# schmatic.net
KiCad netlist of a schematic drawn in Altium Designer
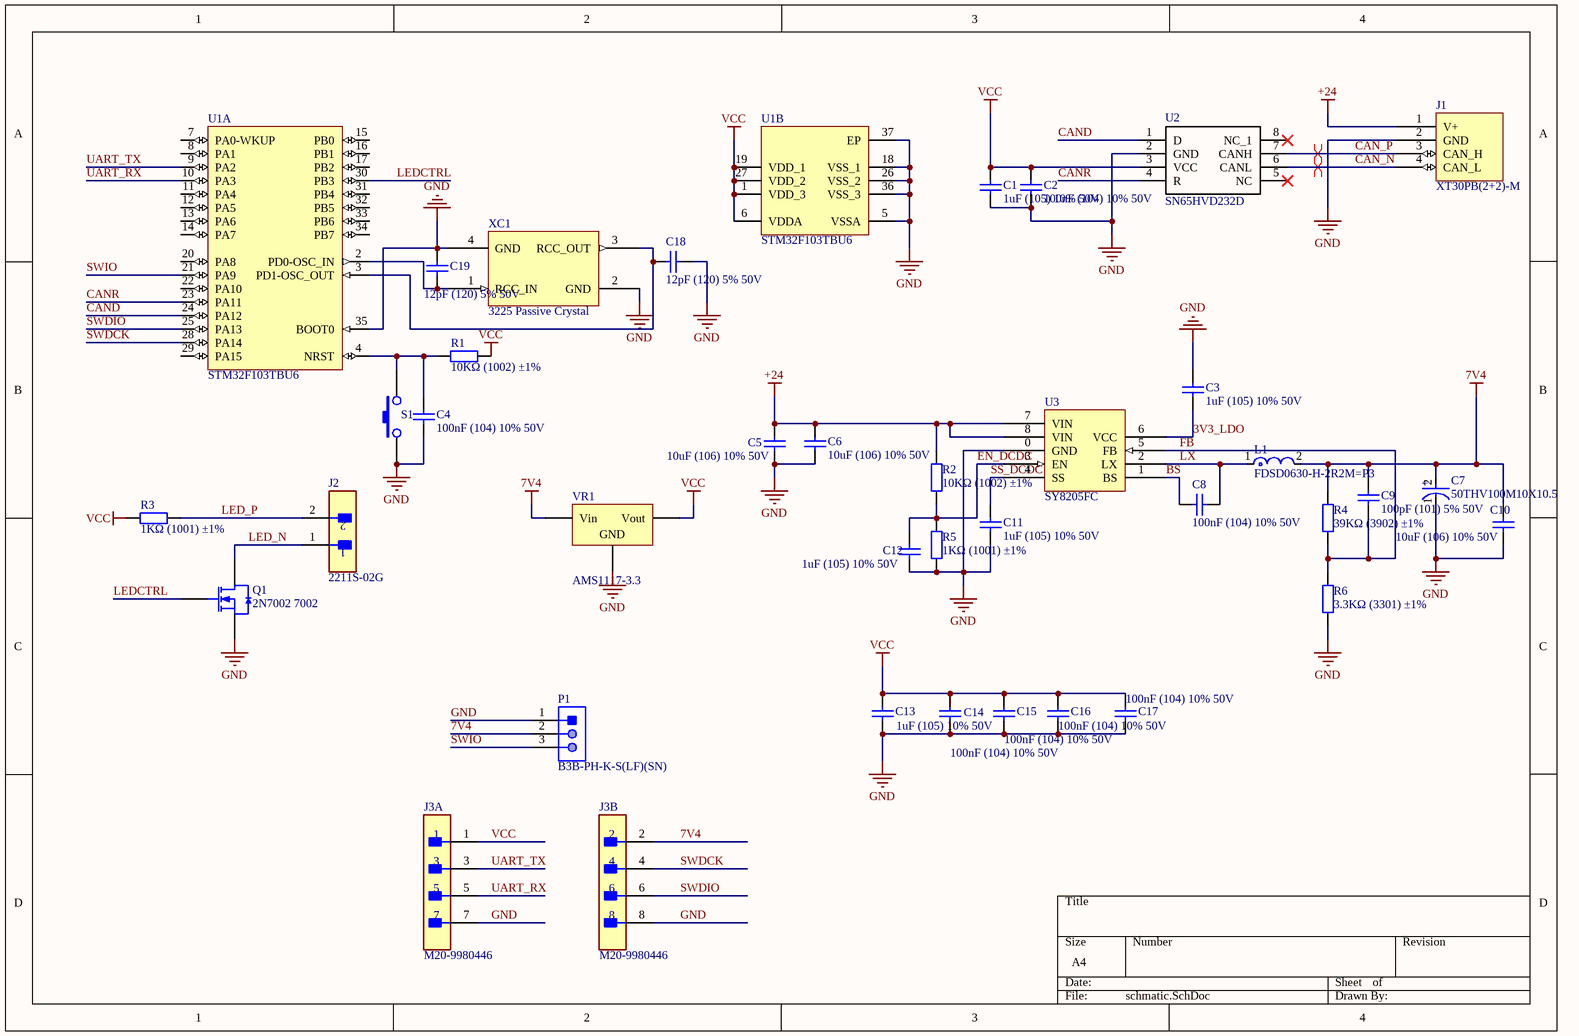
[diagram p0: schmatic.SchDoc]

(export (version "E")
  (design (tool "Eeschema 10.0.6"))
  (components
    (comp (ref "C1")
      (value "1uF (105) 10% 50V")
      (footprint "0603_C")
      (description "贴片电容")
      (libsource (lib "Miscellaneous Devices LC") (part "0603 1uF (105) 10% 50V"))
    )
    (comp (ref "C2")
      (value "100nF (104) 10% 50V")
      (footprint "0603_C")
      (description "贴片电容")
      (libsource (lib "Miscellaneous Devices LC") (part "0603 100nF (104) 10% 50V"))
    )
    (comp (ref "C3")
      (value "1uF (105) 10% 50V")
      (footprint "0603_C")
      (description "贴片电容")
      (libsource (lib "Miscellaneous Devices LC") (part "0603 1uF (105) 10% 50V"))
    )
    (comp (ref "C4")
      (value "100nF (104) 10% 50V")
      (footprint "0603_C")
      (description "贴片电容")
      (libsource (lib "Miscellaneous Devices LC") (part "0603 100nF (104) 10% 50V"))
    )
    (comp (ref "C5")
      (value "10uF (106) 10% 50V")
      (footprint "1206_C")
      (description "贴片电容")
      (libsource (lib "Miscellaneous Devices LC") (part "1206 10uF (106) 10% 50V"))
    )
    (comp (ref "C6")
      (value "10uF (106) 10% 50V")
      (footprint "1206_C")
      (description "贴片电容")
      (libsource (lib "Miscellaneous Devices LC") (part "1206 10uF (106) 10% 50V"))
    )
    (comp (ref "C7")
      (value "50THV100M10X10.5")
      (footprint "FP-THV10X10_5-MFG")
      (description "CAP ALUM 100UF 20% 50V SMD")
      (fields (field (name "VOLTAGE") "50V") (field (name "TOLERANCE") "20%"))
      (libsource (lib "Altium Content Vault") (part "203bc49f2ac43e59fd269a8c329ed05"))
    )
    (comp (ref "C8")
      (value "100nF (104) 10% 50V")
      (footprint "0603_C")
      (description "贴片电容")
      (libsource (lib "Miscellaneous Devices LC") (part "0603 100nF (104) 10% 50V"))
    )
    (comp (ref "C9")
      (value "100pF (101) 5% 50V")
      (footprint "0603_C")
      (description "贴片电容")
      (libsource (lib "Miscellaneous Devices LC") (part "0603 100pF (101) 5% 50V"))
    )
    (comp (ref "C10")
      (value "10uF (106) 10% 50V")
      (footprint "1206_C")
      (description "贴片电容")
      (libsource (lib "Miscellaneous Devices LC") (part "1206 10uF (106) 10% 50V"))
    )
    (comp (ref "C11")
      (value "1uF (105) 10% 50V")
      (footprint "0603_C")
      (description "贴片电容")
      (libsource (lib "Miscellaneous Devices LC") (part "0603 1uF (105) 10% 50V"))
    )
    (comp (ref "C12")
      (value "1uF (105) 10% 50V")
      (footprint "0603_C")
      (description "贴片电容")
      (libsource (lib "Miscellaneous Devices LC") (part "0603 1uF (105) 10% 50V"))
    )
    (comp (ref "C13")
      (value "1uF (105) 10% 50V")
      (footprint "0603_C")
      (description "贴片电容")
      (libsource (lib "Miscellaneous Devices LC") (part "0603 1uF (105) 10% 50V"))
    )
    (comp (ref "C14")
      (value "100nF (104) 10% 50V")
      (footprint "0603_C")
      (description "贴片电容")
      (libsource (lib "Miscellaneous Devices LC") (part "0603 100nF (104) 10% 50V"))
    )
    (comp (ref "C15")
      (value "100nF (104) 10% 50V")
      (footprint "0603_C")
      (description "贴片电容")
      (libsource (lib "Miscellaneous Devices LC") (part "0603 100nF (104) 10% 50V"))
    )
    (comp (ref "C16")
      (value "100nF (104) 10% 50V")
      (footprint "0603_C")
      (description "贴片电容")
      (libsource (lib "Miscellaneous Devices LC") (part "0603 100nF (104) 10% 50V"))
    )
    (comp (ref "C17")
      (value "100nF (104) 10% 50V")
      (footprint "0603_C")
      (description "贴片电容")
      (libsource (lib "Miscellaneous Devices LC") (part "0603 100nF (104) 10% 50V"))
    )
    (comp (ref "C18")
      (value "12pF (120) 5% 50V")
      (footprint "0603_C")
      (description "贴片电容")
      (libsource (lib "Miscellaneous Devices LC") (part "0603 12pF (120) 5% 50V"))
    )
    (comp (ref "C19")
      (value "12pF (120) 5% 50V")
      (footprint "0603_C")
      (description "贴片电容")
      (libsource (lib "Miscellaneous Devices LC") (part "0603 12pF (120) 5% 50V"))
    )
    (comp (ref "J1")
      (value "XT30PB(2+2)-M")
      (footprint "XT30PB(2+2)-M-Footprint-1")
      (description "This is a power connector that can also be used to send/receive can signals")
      (libsource (lib "Skyli Personal Workspace") (part "XT30PB(2+2)-M"))
    )
    (comp (ref "J2")
      (value "2211S-02G")
      (footprint "FP-2211S-02G-MFG")
      (description "2.54mm pitch, single row PCB headers.")
      (libsource (lib "Altium Content Vault") (part "3bc925449376181038e59eaffc5286c"))
    )
    (comp (ref "J3")
      (value "M20-9980446")
      (footprint "FP-M20-9980446-MFG")
      (description "CONN HEADER VERT 8POS 2.54MM")
      (libsource (lib "Altium Content Vault") (part "811e954b9c034aa737de4d9295cbe7e"))
    )
    (comp (ref "L1")
      (value "FDSD0630-H-2R2M=P3")
      (footprint "FP-FDSD0630-MFG")
      (description "FIXED IND 2.2UH 7.1A 17 MOHM SMD")
      (fields (field (name "TOLERANCE") "20%"))
      (libsource (lib "Altium Content Vault") (part "4cc4b267dca4c8e51f7102f422741d8"))
    )
    (comp (ref "P1")
      (value "B3B-PH-K-S(LF)(SN)")
      (footprint "JST-B3B-PH-K-S-3_V")
      (fields (field (name "MANUFACTURER") "JST"))
      (libsource (lib "Altium Content Vault") (part "CN-1P-M-R3"))
    )
    (comp (ref "Q1")
      (value "2N7002 7002")
      (footprint "SOT-23(SOT-23-3)")
      (description "MOS(场效应管)")
      (libsource (lib "Miscellaneous Devices LC") (part "2N7002 7002"))
    )
    (comp (ref "R1")
      (value "10KΩ (1002) ±1%")
      (footprint "0603_R")
      (description "贴片电阻")
      (libsource (lib "") (part "0603 10KΩ (1002) 1%_1"))
    )
    (comp (ref "R2")
      (value "10KΩ (1002) ±1%")
      (footprint "0603_R")
      (description "贴片电阻")
      (libsource (lib "Miscellaneous Devices LC") (part "0603 10KΩ (1002) 1%"))
    )
    (comp (ref "R3")
      (value "1KΩ (1001) ±1%")
      (footprint "0603_R")
      (description "贴片电阻")
      (libsource (lib "") (part "0603 1KΩ (1001) 1%_1"))
    )
    (comp (ref "R4")
      (value "39KΩ (3902) ±1%")
      (footprint "0603_R")
      (description "贴片电阻")
      (libsource (lib "Miscellaneous Devices LC") (part "0603 39KΩ (3902) 1%"))
    )
    (comp (ref "R5")
      (value "1KΩ (1001) ±1%")
      (footprint "0603_R")
      (description "贴片电阻")
      (libsource (lib "Miscellaneous Devices LC") (part "0603 1KΩ (1001) 1%"))
    )
    (comp (ref "R6")
      (value "3.3KΩ (3301) ±1%")
      (footprint "0603_R")
      (description "贴片电阻")
      (libsource (lib "Miscellaneous Devices LC") (part "0603 3.3KΩ (3301) 1%"))
    )
    (comp (ref "S1") (value "按键") (footprint "SWT3*4") (libsource (lib "libadp") (part "Button")))
    (comp (ref "U1")
      (value "STM32F103TBU6")
      (footprint "STM-VFQFPN36_L")
      (libsource (lib "Altium Content Vault") (part "MC-ARM-STM32F103X8_B-SQ37"))
    )
    (comp (ref "U2")
      (value "SN65HVD232D")
      (footprint "SOIC127P600X175-8N")
      (description "3.3-V CAN TRANSCEIVER")
      (fields (field (name "MOUSER PART NUMBER") "595-SN65HVD232D") (field (name "RS PART NUMBER") "1977506"))
      (libsource (lib "libadp") (part "SN65HVD232D"))
    )
    (comp (ref "U3")
      (value "SY8205FC")
      (footprint "SOP-8_EP_150mil")
      (description "5A, 4.5V-30V Input, Synchronous Step Down Regulator (Buck)")
      (libsource (lib "libadp") (part "SY8205FC"))
    )
    (comp (ref "VR1")
      (value "AMS1117-3.3")
      (footprint "SOT-223")
      (description "低压差线性稳压(LDO)")
      (libsource (lib "Miscellaneous Devices LC") (part "SOT-223 AMS1117-3.3"))
    )
    (comp (ref "XC1")
      (value "3225 Passive Crystal")
      (footprint "SMD-3225")
      (libsource (lib "libadp") (part "3225 Passive Crystal"))
    )
  )
  (nets
    (net (code "1") (name "+24") (class "Default")
      (node (ref "C5") (pin "2") (pinfunction "2_2") (pintype "passive"))
      (node (ref "C6") (pin "2") (pinfunction "2_2") (pintype "passive"))
      (node (ref "J1") (pin "1") (pinfunction "V+_1") (pintype "power_in"))
      (node (ref "R2") (pin "2") (pinfunction "2_2") (pintype "passive"))
      (node (ref "U3") (pin "7") (pinfunction "VIN_7") (pintype "power_in"))
      (node (ref "U3") (pin "8") (pinfunction "VIN_8") (pintype "power_in"))
    )
    (net (code "2") (name "/3V3_LDO") (class "Default")
      (node (ref "C3") (pin "1") (pinfunction "1_1") (pintype "passive"))
      (node (ref "U3") (pin "6") (pinfunction "VCC_6") (pintype "power_in"))
    )
    (net (code "3") (name "/BS") (class "Default")
      (node (ref "C8") (pin "1") (pinfunction "1_1") (pintype "passive"))
      (node (ref "U3") (pin "1") (pinfunction "BS_1") (pintype "power_in"))
    )
    (net (code "4") (name "/CAND") (class "Default")
      (node (ref "U1") (pin "24") (pinfunction "PA12_24") (pintype "bidirectional"))
      (node (ref "U2") (pin "1") (pinfunction "D_1") (pintype "passive"))
    )
    (net (code "5") (name "/CANR") (class "Default")
      (node (ref "U1") (pin "23") (pinfunction "PA11_23") (pintype "bidirectional"))
      (node (ref "U2") (pin "4") (pinfunction "R_4") (pintype "passive"))
    )
    (net (code "6") (name "/CAN_N") (class "Default")
      (node (ref "J1") (pin "4") (pinfunction "CAN_L_4") (pintype "bidirectional"))
      (node (ref "U2") (pin "6") (pinfunction "CANL_6") (pintype "passive"))
    )
    (net (code "7") (name "/CAN_P") (class "Default")
      (node (ref "J1") (pin "3") (pinfunction "CAN_H_3") (pintype "bidirectional"))
      (node (ref "U2") (pin "7") (pinfunction "CANH_7") (pintype "passive"))
    )
    (net (code "8") (name "/EN_DCDC") (class "Default")
      (node (ref "C12") (pin "2") (pinfunction "2_2") (pintype "passive"))
      (node (ref "R2") (pin "1") (pinfunction "1_1") (pintype "passive"))
      (node (ref "R5") (pin "2") (pinfunction "2_2") (pintype "passive"))
      (node (ref "U3") (pin "3") (pinfunction "EN_3") (pintype "input"))
    )
    (net (code "9") (name "/FB") (class "Default")
      (node (ref "C9") (pin "1") (pinfunction "1_1") (pintype "passive"))
      (node (ref "R4") (pin "1") (pinfunction "1_1") (pintype "passive"))
      (node (ref "R6") (pin "2") (pinfunction "2_2") (pintype "passive"))
      (node (ref "U3") (pin "5") (pinfunction "FB_5") (pintype "input"))
    )
    (net (code "10") (name "/LEDCTRL") (class "Default")
      (node (ref "Q1") (pin "1") (pinfunction "G_1") (pintype "passive"))
      (node (ref "U1") (pin "30") (pinfunction "PB3_30") (pintype "bidirectional"))
    )
    (net (code "11") (name "/LED_N") (class "Default")
      (node (ref "J2") (pin "1") (pinfunction "1_1") (pintype "passive"))
      (node (ref "Q1") (pin "3") (pinfunction "D_3") (pintype "passive"))
    )
    (net (code "12") (name "/LED_P") (class "Default")
      (node (ref "J2") (pin "2") (pinfunction "2_2") (pintype "passive"))
      (node (ref "R3") (pin "1") (pinfunction "1_1") (pintype "passive"))
    )
    (net (code "13") (name "/LX") (class "Default")
      (node (ref "C8") (pin "2") (pinfunction "2_2") (pintype "passive"))
      (node (ref "L1") (pin "1") (pinfunction "1_1") (pintype "passive"))
      (node (ref "U3") (pin "2") (pinfunction "LX_2") (pintype "power_in"))
    )
    (net (code "14") (name "/SS_DCDC") (class "Default")
      (node (ref "C11") (pin "2") (pinfunction "2_2") (pintype "passive"))
      (node (ref "U3") (pin "4") (pinfunction "SS_4") (pintype "power_in"))
    )
    (net (code "15") (name "/SWDCK") (class "Default")
      (node (ref "J3") (pin "4") (pinfunction "4_4") (pintype "passive"))
      (node (ref "U1") (pin "28") (pinfunction "PA14_28") (pintype "bidirectional"))
    )
    (net (code "16") (name "/SWDIO") (class "Default")
      (node (ref "J3") (pin "6") (pinfunction "6_6") (pintype "passive"))
      (node (ref "U1") (pin "25") (pinfunction "PA13_25") (pintype "bidirectional"))
    )
    (net (code "17") (name "/SWIO") (class "Default")
      (node (ref "P1") (pin "3") (pinfunction "3_3") (pintype "passive"))
      (node (ref "U1") (pin "21") (pinfunction "PA9_21") (pintype "bidirectional"))
    )
    (net (code "18") (name "/UART_RX") (class "Default")
      (node (ref "J3") (pin "5") (pinfunction "5_5") (pintype "passive"))
      (node (ref "U1") (pin "10") (pinfunction "PA3_10") (pintype "bidirectional"))
    )
    (net (code "19") (name "/UART_TX") (class "Default")
      (node (ref "J3") (pin "3") (pinfunction "3_3") (pintype "passive"))
      (node (ref "U1") (pin "9") (pinfunction "PA2_9") (pintype "bidirectional"))
    )
    (net (code "20") (name "7V4") (class "Default")
      (node (ref "C10") (pin "2") (pinfunction "2_2") (pintype "passive"))
      (node (ref "C7") (pin "2") (pinfunction "A_2") (pintype "passive"))
      (node (ref "C9") (pin "2") (pinfunction "2_2") (pintype "passive"))
      (node (ref "J3") (pin "2") (pinfunction "2_2") (pintype "passive"))
      (node (ref "L1") (pin "2") (pinfunction "2_2") (pintype "passive"))
      (node (ref "P1") (pin "2") (pinfunction "2_2") (pintype "passive"))
      (node (ref "R4") (pin "2") (pinfunction "2_2") (pintype "passive"))
      (node (ref "VR1") (pin "3") (pinfunction "Vin_3") (pintype "passive"))
    )
    (net (code "21") (name "GND") (class "Default")
      (node (ref "C1") (pin "1") (pinfunction "1_1") (pintype "passive"))
      (node (ref "C10") (pin "1") (pinfunction "1_1") (pintype "passive"))
      (node (ref "C11") (pin "1") (pinfunction "1_1") (pintype "passive"))
      (node (ref "C12") (pin "1") (pinfunction "1_1") (pintype "passive"))
      (node (ref "C13") (pin "1") (pinfunction "1_1") (pintype "passive"))
      (node (ref "C14") (pin "1") (pinfunction "1_1") (pintype "passive"))
      (node (ref "C15") (pin "1") (pinfunction "1_1") (pintype "passive"))
      (node (ref "C16") (pin "1") (pinfunction "1_1") (pintype "passive"))
      (node (ref "C17") (pin "1") (pinfunction "1_1") (pintype "passive"))
      (node (ref "C18") (pin "2") (pinfunction "2_2") (pintype "passive"))
      (node (ref "C19") (pin "2") (pinfunction "2_2") (pintype "passive"))
      (node (ref "C2") (pin "1") (pinfunction "1_1") (pintype "passive"))
      (node (ref "C3") (pin "2") (pinfunction "2_2") (pintype "passive"))
      (node (ref "C4") (pin "1") (pinfunction "1_1") (pintype "passive"))
      (node (ref "C5") (pin "1") (pinfunction "1_1") (pintype "passive"))
      (node (ref "C6") (pin "1") (pinfunction "1_1") (pintype "passive"))
      (node (ref "C7") (pin "1") (pinfunction "C_1") (pintype "passive"))
      (node (ref "J1") (pin "2") (pinfunction "GND_2") (pintype "power_in"))
      (node (ref "J3") (pin "7") (pinfunction "7_7") (pintype "passive"))
      (node (ref "J3") (pin "8") (pinfunction "8_8") (pintype "passive"))
      (node (ref "P1") (pin "1") (pinfunction "1_1") (pintype "passive"))
      (node (ref "Q1") (pin "2") (pinfunction "S_2") (pintype "passive"))
      (node (ref "R5") (pin "1") (pinfunction "1_1") (pintype "passive"))
      (node (ref "R6") (pin "1") (pinfunction "1_1") (pintype "passive"))
      (node (ref "S1") (pin "1") (pinfunction "1_1") (pintype "passive"))
      (node (ref "U1") (pin "18") (pinfunction "VSS_1_18") (pintype "power_in"))
      (node (ref "U1") (pin "26") (pinfunction "VSS_2_26") (pintype "power_in"))
      (node (ref "U1") (pin "35") (pinfunction "BOOT0_35") (pintype "input"))
      (node (ref "U1") (pin "36") (pinfunction "VSS_3_36") (pintype "power_in"))
      (node (ref "U1") (pin "37") (pinfunction "EP_37") (pintype "power_in"))
      (node (ref "U1") (pin "5") (pinfunction "VSSA_5") (pintype "power_in"))
      (node (ref "U2") (pin "2") (pinfunction "GND_2") (pintype "power_in"))
      (node (ref "U3") (pin "0") (pinfunction "GND_0") (pintype "power_in"))
      (node (ref "VR1") (pin "1") (pinfunction "GND_1") (pintype "passive"))
      (node (ref "XC1") (pin "2") (pinfunction "GND_2") (pintype "power_in"))
      (node (ref "XC1") (pin "4") (pinfunction "GND_4") (pintype "power_in"))
    )
    (net (code "22") (name "Net-(U1A-NRST)") (class "Default")
      (node (ref "C4") (pin "2") (pinfunction "2_2") (pintype "passive"))
      (node (ref "R1") (pin "1") (pinfunction "1_1") (pintype "passive"))
      (node (ref "S1") (pin "2") (pinfunction "2_2") (pintype "passive"))
      (node (ref "U1") (pin "4") (pinfunction "NRST_4") (pintype "bidirectional"))
    )
    (net (code "23") (name "Net-(U1A-PD0-OSC_IN)") (class "Default")
      (node (ref "C19") (pin "1") (pinfunction "1_1") (pintype "passive"))
      (node (ref "U1") (pin "2") (pinfunction "PD0-OSC_IN_2") (pintype "output"))
      (node (ref "XC1") (pin "1") (pinfunction "RCC_IN_1") (pintype "input"))
    )
    (net (code "24") (name "Net-(U1A-PD1-OSC_OUT)") (class "Default")
      (node (ref "C18") (pin "1") (pinfunction "1_1") (pintype "passive"))
      (node (ref "U1") (pin "3") (pinfunction "PD1-OSC_OUT_3") (pintype "input"))
      (node (ref "XC1") (pin "3") (pinfunction "RCC_OUT_3") (pintype "output"))
    )
    (net (code "25") (name "VCC") (class "Default")
      (node (ref "C1") (pin "2") (pinfunction "2_2") (pintype "passive"))
      (node (ref "C13") (pin "2") (pinfunction "2_2") (pintype "passive"))
      (node (ref "C14") (pin "2") (pinfunction "2_2") (pintype "passive"))
      (node (ref "C15") (pin "2") (pinfunction "2_2") (pintype "passive"))
      (node (ref "C16") (pin "2") (pinfunction "2_2") (pintype "passive"))
      (node (ref "C17") (pin "2") (pinfunction "2_2") (pintype "passive"))
      (node (ref "C2") (pin "2") (pinfunction "2_2") (pintype "passive"))
      (node (ref "J3") (pin "1") (pinfunction "1_1") (pintype "passive"))
      (node (ref "R1") (pin "2") (pinfunction "2_2") (pintype "passive"))
      (node (ref "R3") (pin "2") (pinfunction "2_2") (pintype "passive"))
      (node (ref "U1") (pin "1") (pinfunction "VDD_3_1") (pintype "power_in"))
      (node (ref "U1") (pin "19") (pinfunction "VDD_1_19") (pintype "power_in"))
      (node (ref "U1") (pin "27") (pinfunction "VDD_2_27") (pintype "power_in"))
      (node (ref "U1") (pin "6") (pinfunction "VDDA_6") (pintype "power_in"))
      (node (ref "U2") (pin "3") (pinfunction "VCC_3") (pintype "power_in"))
      (node (ref "VR1") (pin "2") (pinfunction "Vout_2") (pintype "passive"))
    )
    (net (code "26") (name "unconnected-(U1A-PA0-WKUP-Pad7)") (class "Default")
      (node (ref "U1") (pin "7") (pinfunction "PA0-WKUP_7") (pintype "bidirectional"))
    )
    (net (code "27") (name "unconnected-(U1A-PA1-Pad8)") (class "Default")
      (node (ref "U1") (pin "8") (pinfunction "PA1_8") (pintype "bidirectional"))
    )
    (net (code "28") (name "unconnected-(U1A-PA4-Pad11)") (class "Default")
      (node (ref "U1") (pin "11") (pinfunction "PA4_11") (pintype "bidirectional"))
    )
    (net (code "29") (name "unconnected-(U1A-PA5-Pad12)") (class "Default")
      (node (ref "U1") (pin "12") (pinfunction "PA5_12") (pintype "bidirectional"))
    )
    (net (code "30") (name "unconnected-(U1A-PA6-Pad13)") (class "Default")
      (node (ref "U1") (pin "13") (pinfunction "PA6_13") (pintype "bidirectional"))
    )
    (net (code "31") (name "unconnected-(U1A-PA7-Pad14)") (class "Default")
      (node (ref "U1") (pin "14") (pinfunction "PA7_14") (pintype "bidirectional"))
    )
    (net (code "32") (name "unconnected-(U1A-PA8-Pad20)") (class "Default")
      (node (ref "U1") (pin "20") (pinfunction "PA8_20") (pintype "bidirectional"))
    )
    (net (code "33") (name "unconnected-(U1A-PA10-Pad22)") (class "Default")
      (node (ref "U1") (pin "22") (pinfunction "PA10_22") (pintype "bidirectional"))
    )
    (net (code "34") (name "unconnected-(U1A-PA15-Pad29)") (class "Default")
      (node (ref "U1") (pin "29") (pinfunction "PA15_29") (pintype "bidirectional"))
    )
    (net (code "35") (name "unconnected-(U1A-PB0-Pad15)") (class "Default")
      (node (ref "U1") (pin "15") (pinfunction "PB0_15") (pintype "bidirectional"))
    )
    (net (code "36") (name "unconnected-(U1A-PB1-Pad16)") (class "Default")
      (node (ref "U1") (pin "16") (pinfunction "PB1_16") (pintype "bidirectional"))
    )
    (net (code "37") (name "unconnected-(U1A-PB2-Pad17)") (class "Default")
      (node (ref "U1") (pin "17") (pinfunction "PB2_17") (pintype "bidirectional"))
    )
    (net (code "38") (name "unconnected-(U1A-PB4-Pad31)") (class "Default")
      (node (ref "U1") (pin "31") (pinfunction "PB4_31") (pintype "bidirectional"))
    )
    (net (code "39") (name "unconnected-(U1A-PB5-Pad32)") (class "Default")
      (node (ref "U1") (pin "32") (pinfunction "PB5_32") (pintype "bidirectional"))
    )
    (net (code "40") (name "unconnected-(U1A-PB6-Pad33)") (class "Default")
      (node (ref "U1") (pin "33") (pinfunction "PB6_33") (pintype "bidirectional"))
    )
    (net (code "41") (name "unconnected-(U1A-PB7-Pad34)") (class "Default")
      (node (ref "U1") (pin "34") (pinfunction "PB7_34") (pintype "bidirectional"))
    )
    (net (code "42") (name "unconnected-(U2-NC-Pad5)") (class "Default")
      (node (ref "U2") (pin "5") (pinfunction "NC_5") (pintype "passive+no_connect"))
    )
    (net (code "43") (name "unconnected-(U2-NC_1-Pad8)") (class "Default")
      (node (ref "U2") (pin "8") (pinfunction "NC_1_8") (pintype "passive+no_connect"))
    )
  )
)
